# CAR_schematic_design.net
KiCad netlist of a schematic drawn in EAGLE
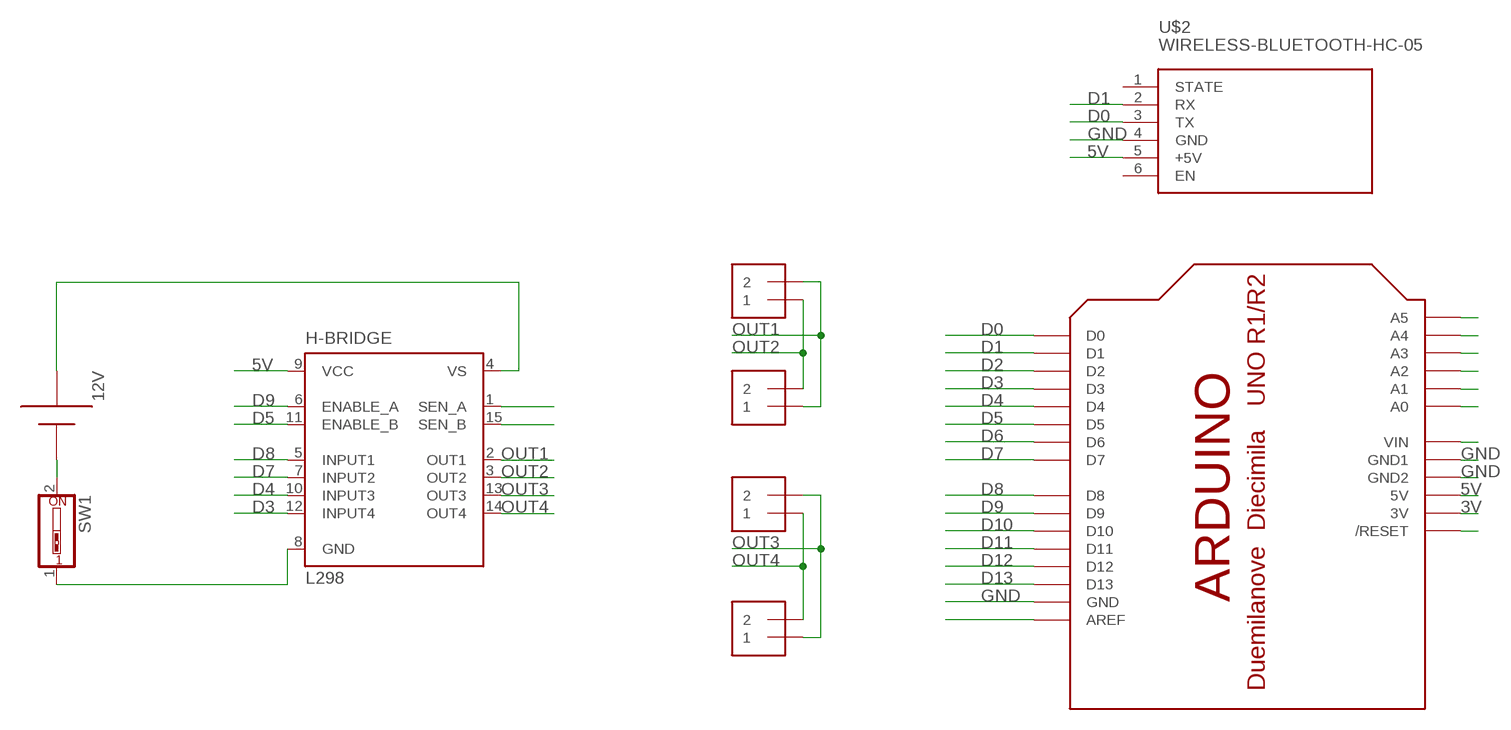
[diagram p0: schematic, sheet 1]

(export (version "E")
  (design (tool "Eeschema 10.0.6"))
  (components
    (comp (ref "12V")
      (value "AAA")
      (footprint "eagle-import:12BH412")
      (libsource (lib "eagle-import") (part "AAA"))
    )
    (comp (ref "H-BRIDGE")
      (value "L298")
      (footprint "eagle-import:MULTIWATT-15")
      (fields (field (name "MPN") "L298N"))
      (libsource (lib "eagle-import") (part "L298"))
    )
    (comp (ref "MOTOA1")
      (value "1X2-3.5MM")
      (footprint "eagle-import:1X2-3.5MM")
      (libsource (lib "eagle-import") (part "1X2-3.5MM"))
    )
    (comp (ref "MOTORA2")
      (value "1X2-3.5MM")
      (footprint "eagle-import:1X2-3.5MM")
      (libsource (lib "eagle-import") (part "1X2-3.5MM"))
    )
    (comp (ref "MOTORB1")
      (value "1X2-3.5MM")
      (footprint "eagle-import:1X2-3.5MM")
      (libsource (lib "eagle-import") (part "1X2-3.5MM"))
    )
    (comp (ref "MOTORB2")
      (value "1X2-3.5MM")
      (footprint "eagle-import:1X2-3.5MM")
      (libsource (lib "eagle-import") (part "1X2-3.5MM"))
    )
    (comp (ref "SW1")
      (value "SW_DIP-1")
      (footprint "eagle-import:EDG-01")
      (libsource (lib "eagle-import") (part "SW_DIP-1"))
    )
    (comp (ref "U$1")
      (value "ARDUINO-NOHOLE")
      (footprint "eagle-import:ARDUINO-NOHOLE")
      (libsource (lib "eagle-import") (part "ARDUINO-NOHOLE"))
    )
    (comp (ref "U$2")
      (value "WIRELESS-BLUETOOTH-HC-05")
      (footprint "eagle-import:WIRELESS-BLUETOOTH-HC-05")
      (libsource (lib "eagle-import") (part "WIRELESS-BLUETOOTH-HC-05"))
    )
  )
  (nets
    (net (code "1") (name "/3V") (class "Default")
      (node (ref "U$1") (pin "3V") (pinfunction "3V_3V") (pintype "power_in"))
    )
    (net (code "2") (name "/5V") (class "Default")
      (node (ref "H-BRIDGE") (pin "9") (pinfunction "VCC_9") (pintype "power_in"))
      (node (ref "U$1") (pin "5V") (pinfunction "5V_5V") (pintype "power_in"))
      (node (ref "U$2") (pin "5") (pinfunction "+5V_5") (pintype "power_in"))
    )
    (net (code "3") (name "/D0") (class "Default")
      (node (ref "U$1") (pin "D0") (pinfunction "D0_D0") (pintype "bidirectional"))
      (node (ref "U$2") (pin "3") (pinfunction "TX_3") (pintype "bidirectional"))
    )
    (net (code "4") (name "/D1") (class "Default")
      (node (ref "U$1") (pin "D1") (pinfunction "D1_D1") (pintype "bidirectional"))
      (node (ref "U$2") (pin "2") (pinfunction "RX_2") (pintype "bidirectional"))
    )
    (net (code "5") (name "/D2") (class "Default")
      (node (ref "U$1") (pin "D2") (pinfunction "D2_D2") (pintype "bidirectional"))
    )
    (net (code "6") (name "/D3") (class "Default")
      (node (ref "H-BRIDGE") (pin "12") (pinfunction "INPUT4_12") (pintype "input"))
      (node (ref "U$1") (pin "D3") (pinfunction "D3_D3") (pintype "bidirectional"))
    )
    (net (code "7") (name "/D4") (class "Default")
      (node (ref "H-BRIDGE") (pin "10") (pinfunction "INPUT3_10") (pintype "input"))
      (node (ref "U$1") (pin "D4") (pinfunction "D4_D4") (pintype "bidirectional"))
    )
    (net (code "8") (name "/D5") (class "Default")
      (node (ref "H-BRIDGE") (pin "11") (pinfunction "ENABLE_B_11") (pintype "input"))
      (node (ref "U$1") (pin "D5") (pinfunction "D5_D5") (pintype "bidirectional"))
    )
    (net (code "9") (name "/D6") (class "Default")
      (node (ref "U$1") (pin "D6") (pinfunction "D6_D6") (pintype "bidirectional"))
    )
    (net (code "10") (name "/D7") (class "Default")
      (node (ref "H-BRIDGE") (pin "7") (pinfunction "INPUT2_7") (pintype "input"))
      (node (ref "U$1") (pin "D7") (pinfunction "D7_D7") (pintype "bidirectional"))
    )
    (net (code "11") (name "/D8") (class "Default")
      (node (ref "H-BRIDGE") (pin "5") (pinfunction "INPUT1_5") (pintype "input"))
      (node (ref "U$1") (pin "D8") (pinfunction "D8_D8") (pintype "bidirectional"))
    )
    (net (code "12") (name "/D9") (class "Default")
      (node (ref "H-BRIDGE") (pin "6") (pinfunction "ENABLE_A_6") (pintype "input"))
      (node (ref "U$1") (pin "D9") (pinfunction "D9_D9") (pintype "bidirectional"))
    )
    (net (code "13") (name "/D10") (class "Default")
      (node (ref "U$1") (pin "D10") (pinfunction "D10_D10") (pintype "bidirectional"))
    )
    (net (code "14") (name "/D11") (class "Default")
      (node (ref "U$1") (pin "D11") (pinfunction "D11_D11") (pintype "bidirectional"))
    )
    (net (code "15") (name "/D12") (class "Default")
      (node (ref "U$1") (pin "D12") (pinfunction "D12_D12") (pintype "bidirectional"))
    )
    (net (code "16") (name "/D13") (class "Default")
      (node (ref "U$1") (pin "D13") (pinfunction "D13_D13") (pintype "bidirectional"))
    )
    (net (code "17") (name "/GND") (class "Default")
      (node (ref "U$1") (pin "GND") (pinfunction "GND_GND") (pintype "power_in"))
      (node (ref "U$1") (pin "GND1") (pinfunction "GND1_GND1") (pintype "power_in"))
      (node (ref "U$1") (pin "GND2") (pinfunction "GND2_GND2") (pintype "power_in"))
      (node (ref "U$2") (pin "4") (pinfunction "GND_4") (pintype "power_in"))
    )
    (net (code "18") (name "/OUT1") (class "Default")
      (node (ref "H-BRIDGE") (pin "2") (pinfunction "OUT1_2") (pintype "output"))
      (node (ref "MOTOA1") (pin "2") (pinfunction "2_2") (pintype "passive"))
      (node (ref "MOTORA2") (pin "1") (pinfunction "1_1") (pintype "passive"))
    )
    (net (code "19") (name "/OUT2") (class "Default")
      (node (ref "H-BRIDGE") (pin "3") (pinfunction "OUT2_3") (pintype "output"))
      (node (ref "MOTOA1") (pin "1") (pinfunction "1_1") (pintype "passive"))
      (node (ref "MOTORA2") (pin "2") (pinfunction "2_2") (pintype "passive"))
    )
    (net (code "20") (name "/OUT3") (class "Default")
      (node (ref "H-BRIDGE") (pin "13") (pinfunction "OUT3_13") (pintype "output"))
      (node (ref "MOTORB1") (pin "2") (pinfunction "2_2") (pintype "passive"))
      (node (ref "MOTORB2") (pin "1") (pinfunction "1_1") (pintype "passive"))
    )
    (net (code "21") (name "/OUT4") (class "Default")
      (node (ref "H-BRIDGE") (pin "14") (pinfunction "OUT4_14") (pintype "output"))
      (node (ref "MOTORB1") (pin "1") (pinfunction "1_1") (pintype "passive"))
      (node (ref "MOTORB2") (pin "2") (pinfunction "2_2") (pintype "passive"))
    )
    (net (code "22") (name "Net-(12V-Pad+)") (class "Default")
      (node (ref "12V") (pin "+") (pinfunction "+_+") (pintype "bidirectional"))
      (node (ref "SW1") (pin "2") (pinfunction "2_2") (pintype "passive"))
    )
    (net (code "23") (name "Net-(H-BRIDGE-GND)") (class "Default")
      (node (ref "H-BRIDGE") (pin "8") (pinfunction "GND_8") (pintype "power_in"))
      (node (ref "SW1") (pin "1") (pinfunction "1_1") (pintype "passive"))
    )
    (net (code "24") (name "Net-(H-BRIDGE-VS)") (class "Default")
      (node (ref "12V") (pin "-") (pinfunction "-_-") (pintype "bidirectional"))
      (node (ref "H-BRIDGE") (pin "4") (pinfunction "VS_4") (pintype "power_in"))
    )
    (net (code "25") (name "unconnected-(H-BRIDGE-SEN_A-Pad1)") (class "Default")
      (node (ref "H-BRIDGE") (pin "1") (pinfunction "SEN_A_1") (pintype "input"))
    )
    (net (code "26") (name "unconnected-(H-BRIDGE-SEN_B-Pad15)") (class "Default")
      (node (ref "H-BRIDGE") (pin "15") (pinfunction "SEN_B_15") (pintype "input"))
    )
    (net (code "27") (name "unconnected-(U$1-PadA0)") (class "Default")
      (node (ref "U$1") (pin "A0") (pinfunction "A0_A0") (pintype "bidirectional"))
    )
    (net (code "28") (name "unconnected-(U$1-PadA1)") (class "Default")
      (node (ref "U$1") (pin "A1") (pinfunction "A1_A1") (pintype "bidirectional"))
    )
    (net (code "29") (name "unconnected-(U$1-PadA2)") (class "Default")
      (node (ref "U$1") (pin "A2") (pinfunction "A2_A2") (pintype "bidirectional"))
    )
    (net (code "30") (name "unconnected-(U$1-PadA3)") (class "Default")
      (node (ref "U$1") (pin "A3") (pinfunction "A3_A3") (pintype "bidirectional"))
    )
    (net (code "31") (name "unconnected-(U$1-PadA4)") (class "Default")
      (node (ref "U$1") (pin "A4") (pinfunction "A4_A4") (pintype "bidirectional"))
    )
    (net (code "32") (name "unconnected-(U$1-PadA5)") (class "Default")
      (node (ref "U$1") (pin "A5") (pinfunction "A5_A5") (pintype "bidirectional"))
    )
    (net (code "33") (name "unconnected-(U$1-PadAREF)") (class "Default")
      (node (ref "U$1") (pin "AREF") (pinfunction "AREF_AREF") (pintype "bidirectional"))
    )
    (net (code "34") (name "unconnected-(U$1-PadVIN)") (class "Default")
      (node (ref "U$1") (pin "VIN") (pinfunction "VIN_VIN") (pintype "power_in"))
    )
    (net (code "35") (name "unconnected-(U$1-{slash}RESET-PadRESET)") (class "Default")
      (node (ref "U$1") (pin "RESET") (pinfunction "/RESET_RESET") (pintype "bidirectional"))
    )
    (net (code "36") (name "unconnected-(U$2-EN-Pad6)") (class "Default")
      (node (ref "U$2") (pin "6") (pinfunction "EN_6") (pintype "bidirectional"))
    )
    (net (code "37") (name "unconnected-(U$2-STATE-Pad1)") (class "Default")
      (node (ref "U$2") (pin "1") (pinfunction "STATE_1") (pintype "bidirectional"))
    )
  )
)
